# PanTiltCtlBoard.net
KiCad netlist of a schematic drawn in EAGLE
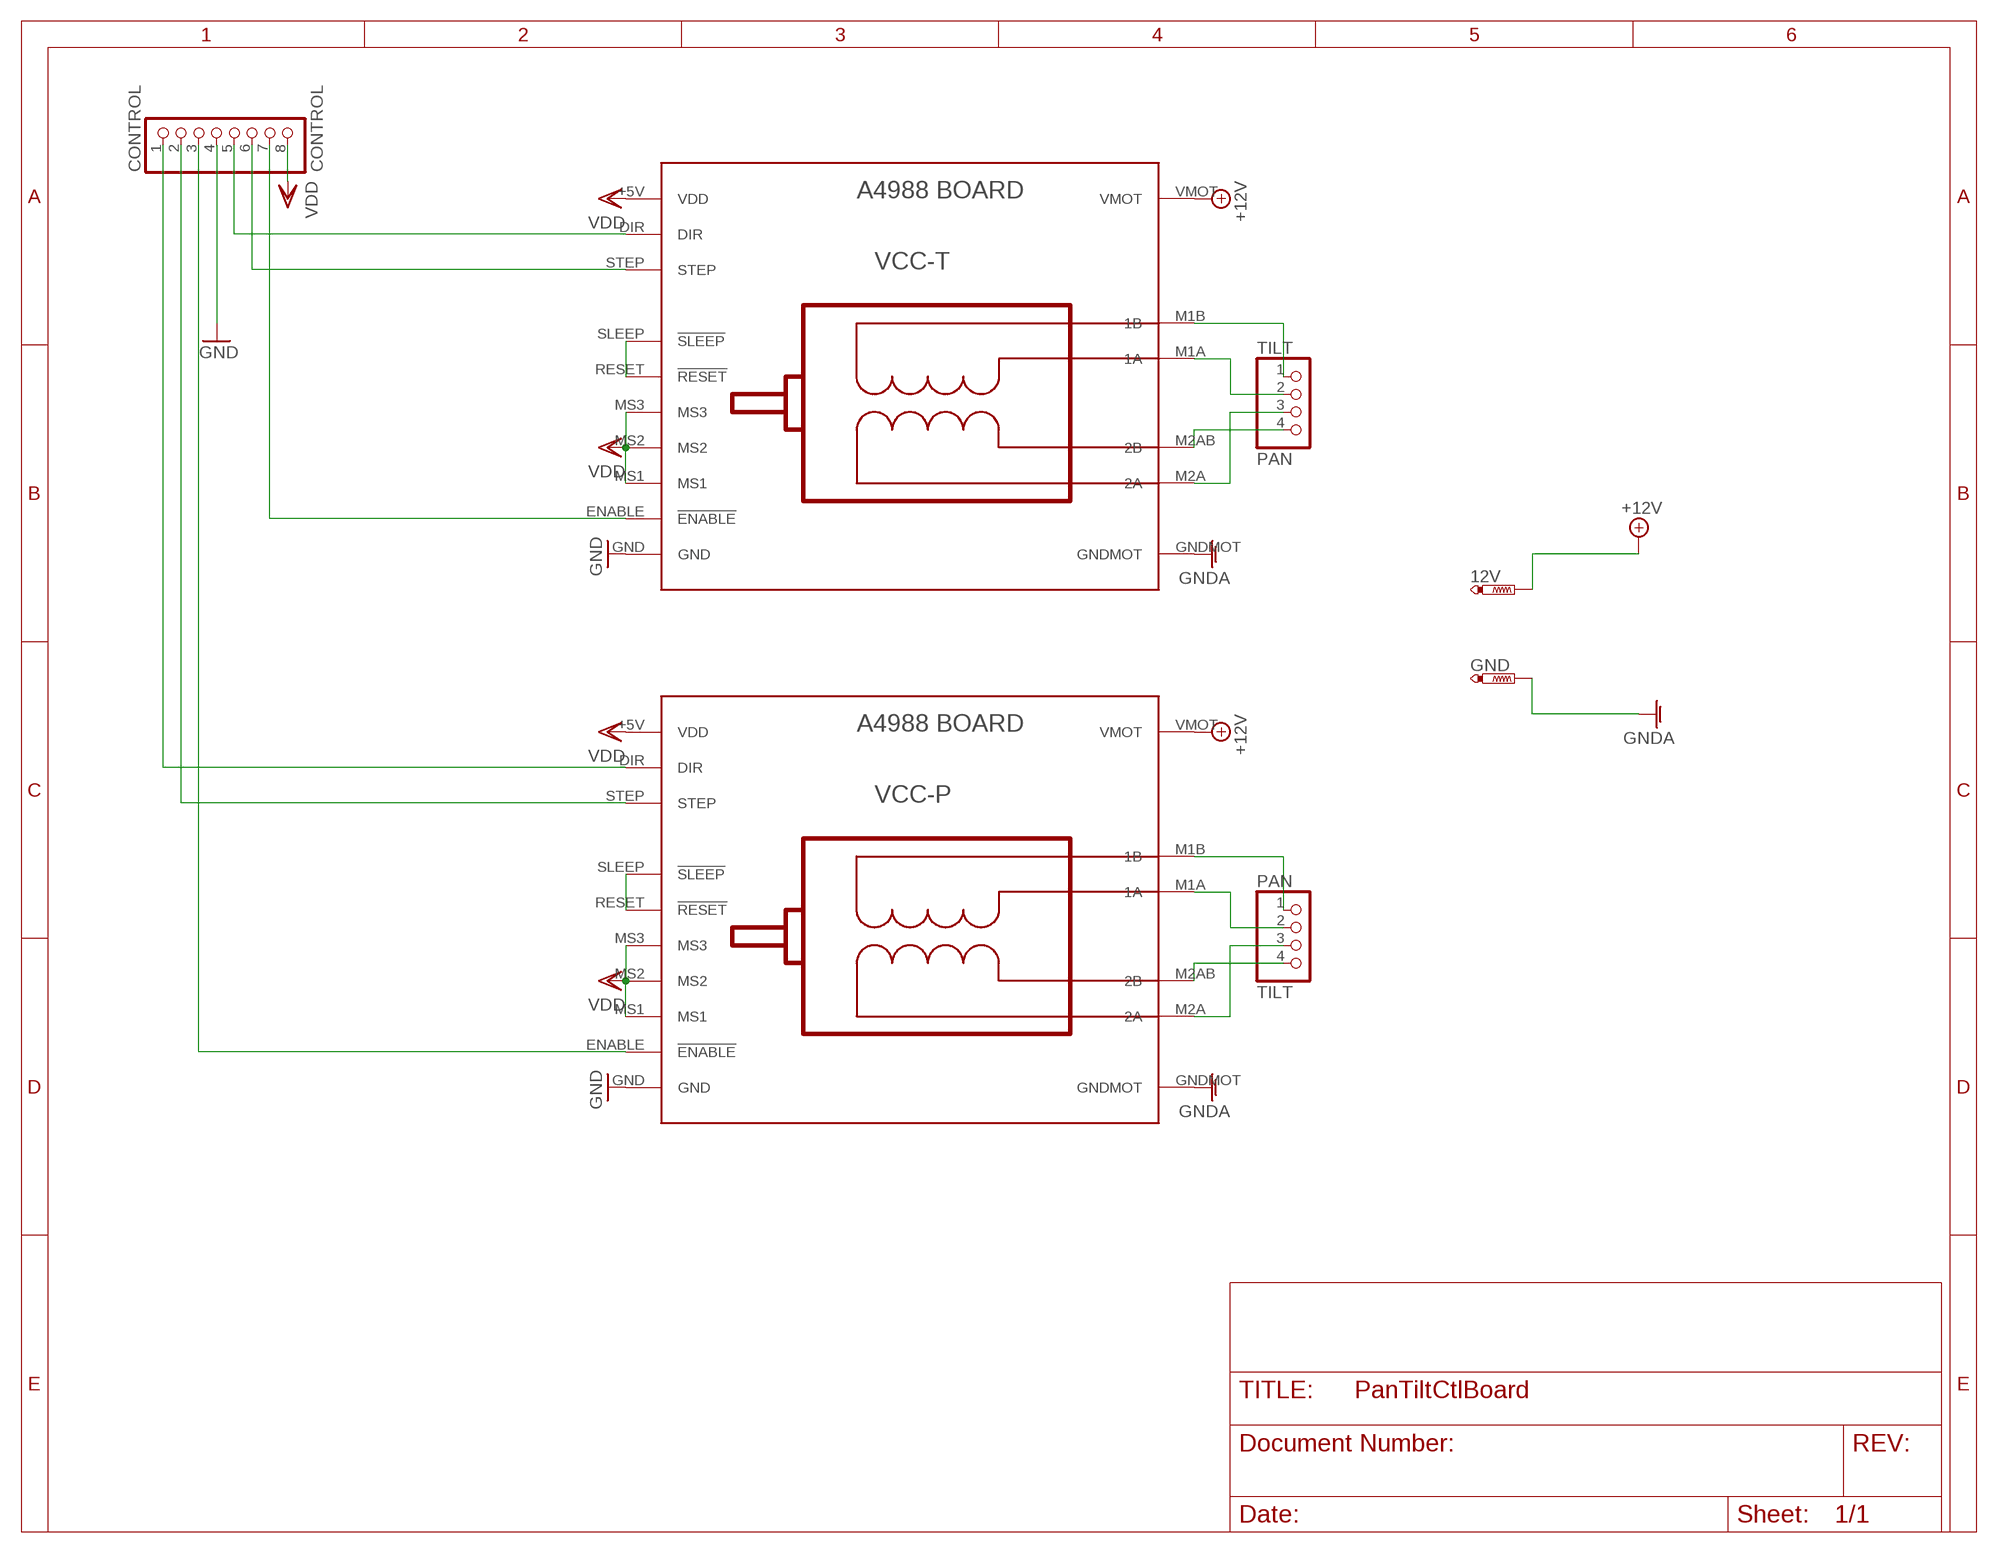
[diagram p0: schematic, sheet 1]

(export (version "E")
  (design (tool "Eeschema 10.0.6"))
  (components
    (comp (ref "12V")
      (value "PTR1PAD1-13Y")
      (footprint "eagle-import:P1-13Y")
      (libsource (lib "eagle-import") (part "PTR1PAD1-13Y"))
    )
    (comp (ref "CONTROL")
      (value "CONTROL")
      (footprint "eagle-import:1X08")
      (libsource (lib "eagle-import") (part "PINHD-1X8"))
    )
    (comp (ref "GND")
      (value "PTR1PAD1-13Y")
      (footprint "eagle-import:P1-13Y")
      (libsource (lib "eagle-import") (part "PTR1PAD1-13Y"))
    )
    (comp (ref "PAN")
      (value "TILT")
      (footprint "eagle-import:1X04")
      (libsource (lib "eagle-import") (part "PINHD-1X4"))
    )
    (comp (ref "TILT")
      (value "PAN")
      (footprint "eagle-import:1X04")
      (libsource (lib "eagle-import") (part "PINHD-1X4"))
    )
    (comp (ref "VCC-P")
      (value "BOARD_A4988")
      (footprint "eagle-import:BOARD_A4988")
      (libsource (lib "eagle-import") (part "BOARD_A4988"))
    )
    (comp (ref "VCC-T")
      (value "BOARD_A4988")
      (footprint "eagle-import:BOARD_A4988")
      (libsource (lib "eagle-import") (part "BOARD_A4988"))
    )
  )
  (nets
    (net (code "1") (name "+12V") (class "Default")
      (node (ref "12V") (pin "TP") (pinfunction "TP_TP") (pintype "input"))
      (node (ref "VCC-P") (pin "VMOT") (pinfunction "VMOT_VMOT") (pintype "power_in"))
      (node (ref "VCC-T") (pin "VMOT") (pinfunction "VMOT_VMOT") (pintype "power_in"))
    )
    (net (code "2") (name "GND") (class "Default")
      (node (ref "CONTROL") (pin "4") (pinfunction "4_4") (pintype "passive"))
      (node (ref "VCC-P") (pin "GND") (pinfunction "GND_GND") (pintype "power_in"))
      (node (ref "VCC-T") (pin "GND") (pinfunction "GND_GND") (pintype "power_in"))
    )
    (net (code "3") (name "GNDA") (class "Default")
      (node (ref "GND") (pin "TP") (pinfunction "TP_TP") (pintype "input"))
      (node (ref "VCC-P") (pin "GNDMOT") (pinfunction "GNDMOT_GNDMOT") (pintype "power_in"))
      (node (ref "VCC-T") (pin "GNDMOT") (pinfunction "GNDMOT_GNDMOT") (pintype "power_in"))
    )
    (net (code "4") (name "Net-(CONTROL-Pad1)") (class "Default")
      (node (ref "CONTROL") (pin "1") (pinfunction "1_1") (pintype "passive"))
      (node (ref "VCC-P") (pin "DIR") (pinfunction "DIR_DIR") (pintype "input"))
    )
    (net (code "5") (name "Net-(CONTROL-Pad2)") (class "Default")
      (node (ref "CONTROL") (pin "2") (pinfunction "2_2") (pintype "passive"))
      (node (ref "VCC-P") (pin "STEP") (pinfunction "STEP_STEP") (pintype "input"))
    )
    (net (code "6") (name "Net-(CONTROL-Pad5)") (class "Default")
      (node (ref "CONTROL") (pin "5") (pinfunction "5_5") (pintype "passive"))
      (node (ref "VCC-T") (pin "DIR") (pinfunction "DIR_DIR") (pintype "input"))
    )
    (net (code "7") (name "Net-(CONTROL-Pad6)") (class "Default")
      (node (ref "CONTROL") (pin "6") (pinfunction "6_6") (pintype "passive"))
      (node (ref "VCC-T") (pin "STEP") (pinfunction "STEP_STEP") (pintype "input"))
    )
    (net (code "8") (name "Net-(VCC-P-1A)") (class "Default")
      (node (ref "PAN") (pin "2") (pinfunction "2_2") (pintype "passive"))
      (node (ref "VCC-P") (pin "M1A") (pinfunction "1A_M1A") (pintype "output"))
    )
    (net (code "9") (name "Net-(VCC-P-1B)") (class "Default")
      (node (ref "PAN") (pin "1") (pinfunction "1_1") (pintype "passive"))
      (node (ref "VCC-P") (pin "M1B") (pinfunction "1B_M1B") (pintype "output"))
    )
    (net (code "10") (name "Net-(VCC-P-2A)") (class "Default")
      (node (ref "PAN") (pin "3") (pinfunction "3_3") (pintype "passive"))
      (node (ref "VCC-P") (pin "M2A") (pinfunction "2A_M2A") (pintype "output"))
    )
    (net (code "11") (name "Net-(VCC-P-2B)") (class "Default")
      (node (ref "PAN") (pin "4") (pinfunction "4_4") (pintype "passive"))
      (node (ref "VCC-P") (pin "M2AB") (pinfunction "2B_M2AB") (pintype "output"))
    )
    (net (code "12") (name "Net-(VCC-P-~{ENABLE})") (class "Default")
      (node (ref "CONTROL") (pin "3") (pinfunction "3_3") (pintype "passive"))
      (node (ref "VCC-P") (pin "ENABLE") (pinfunction "~{ENABLE}_ENABLE") (pintype "input"))
    )
    (net (code "13") (name "Net-(VCC-P-~{RESET})") (class "Default")
      (node (ref "VCC-P") (pin "RESET") (pinfunction "~{RESET}_RESET") (pintype "input"))
      (node (ref "VCC-P") (pin "SLEEP") (pinfunction "~{SLEEP}_SLEEP") (pintype "input"))
    )
    (net (code "14") (name "Net-(VCC-T-1A)") (class "Default")
      (node (ref "TILT") (pin "2") (pinfunction "2_2") (pintype "passive"))
      (node (ref "VCC-T") (pin "M1A") (pinfunction "1A_M1A") (pintype "output"))
    )
    (net (code "15") (name "Net-(VCC-T-1B)") (class "Default")
      (node (ref "TILT") (pin "1") (pinfunction "1_1") (pintype "passive"))
      (node (ref "VCC-T") (pin "M1B") (pinfunction "1B_M1B") (pintype "output"))
    )
    (net (code "16") (name "Net-(VCC-T-2A)") (class "Default")
      (node (ref "TILT") (pin "3") (pinfunction "3_3") (pintype "passive"))
      (node (ref "VCC-T") (pin "M2A") (pinfunction "2A_M2A") (pintype "output"))
    )
    (net (code "17") (name "Net-(VCC-T-2B)") (class "Default")
      (node (ref "TILT") (pin "4") (pinfunction "4_4") (pintype "passive"))
      (node (ref "VCC-T") (pin "M2AB") (pinfunction "2B_M2AB") (pintype "output"))
    )
    (net (code "18") (name "Net-(VCC-T-~{ENABLE})") (class "Default")
      (node (ref "CONTROL") (pin "7") (pinfunction "7_7") (pintype "passive"))
      (node (ref "VCC-T") (pin "ENABLE") (pinfunction "~{ENABLE}_ENABLE") (pintype "input"))
    )
    (net (code "19") (name "Net-(VCC-T-~{RESET})") (class "Default")
      (node (ref "VCC-T") (pin "RESET") (pinfunction "~{RESET}_RESET") (pintype "input"))
      (node (ref "VCC-T") (pin "SLEEP") (pinfunction "~{SLEEP}_SLEEP") (pintype "input"))
    )
    (net (code "20") (name "VDD") (class "Default")
      (node (ref "CONTROL") (pin "8") (pinfunction "8_8") (pintype "passive"))
      (node (ref "VCC-P") (pin "+5V") (pinfunction "VDD_+5V") (pintype "power_in"))
      (node (ref "VCC-P") (pin "MS1") (pinfunction "MS1_MS1") (pintype "input"))
      (node (ref "VCC-P") (pin "MS2") (pinfunction "MS2_MS2") (pintype "input"))
      (node (ref "VCC-P") (pin "MS3") (pinfunction "MS3_MS3") (pintype "input"))
      (node (ref "VCC-T") (pin "+5V") (pinfunction "VDD_+5V") (pintype "power_in"))
      (node (ref "VCC-T") (pin "MS1") (pinfunction "MS1_MS1") (pintype "input"))
      (node (ref "VCC-T") (pin "MS2") (pinfunction "MS2_MS2") (pintype "input"))
      (node (ref "VCC-T") (pin "MS3") (pinfunction "MS3_MS3") (pintype "input"))
    )
  )
)
